# Top_module.net
KiCad netlist of a schematic drawn in EAGLE
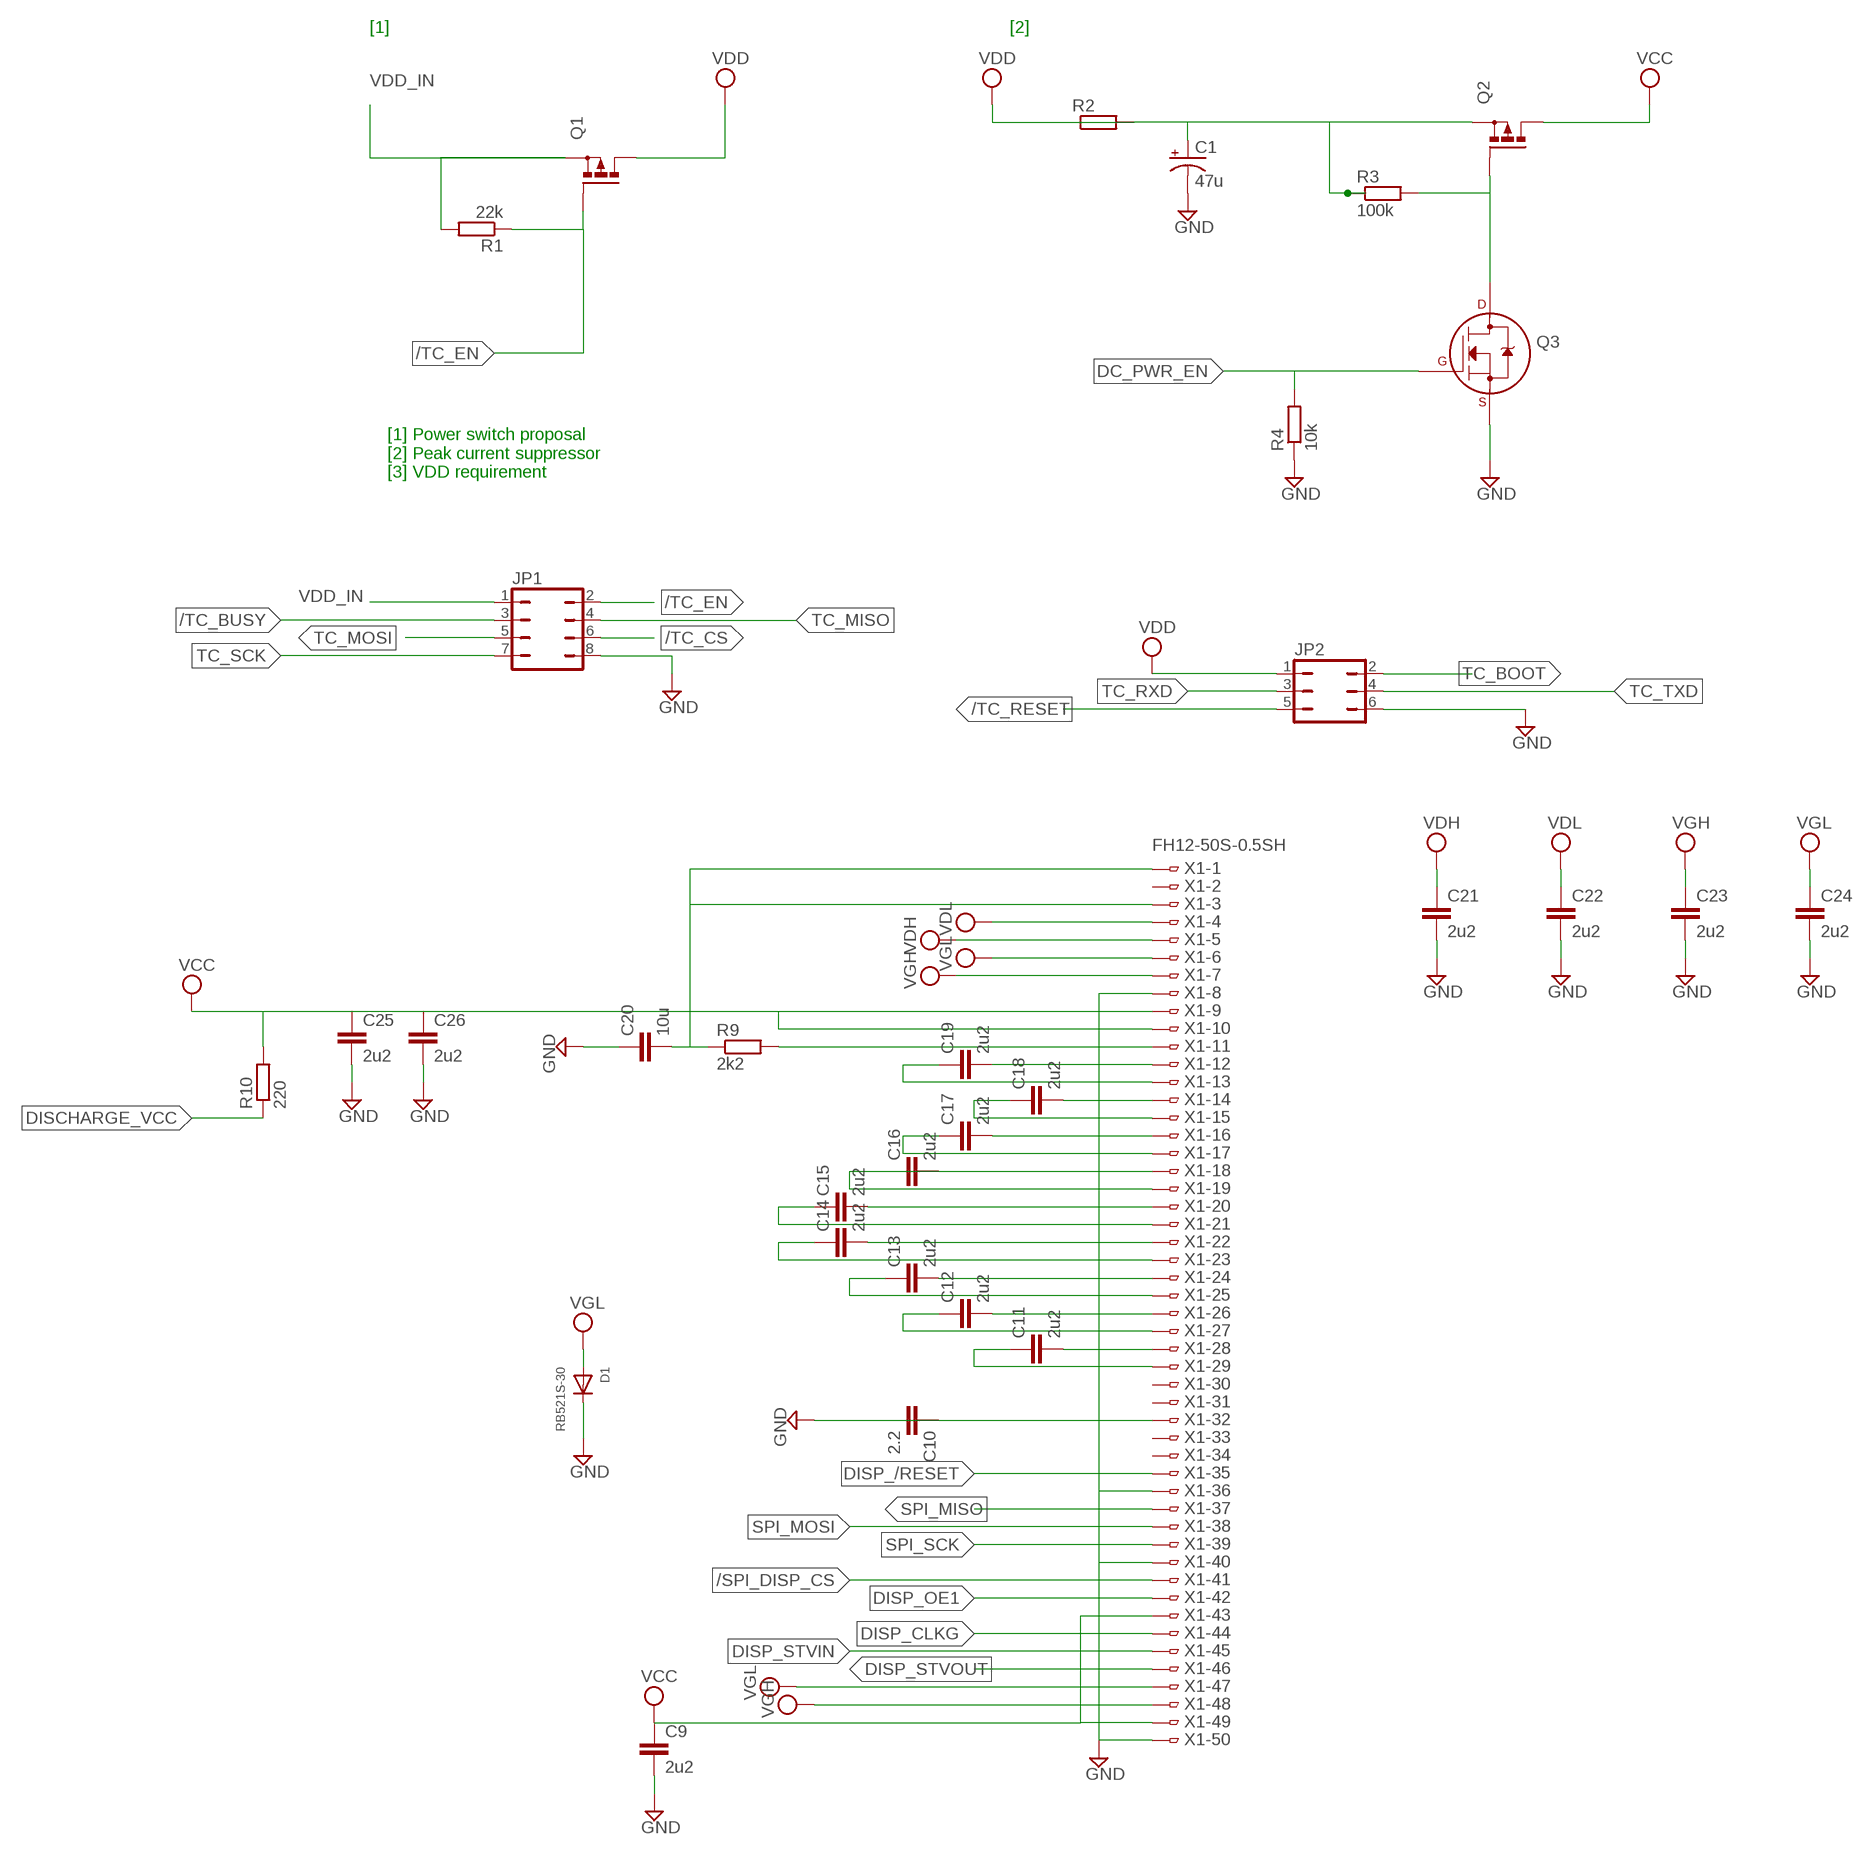
[diagram p0: schematic, sheet 1, part 1 of 2]
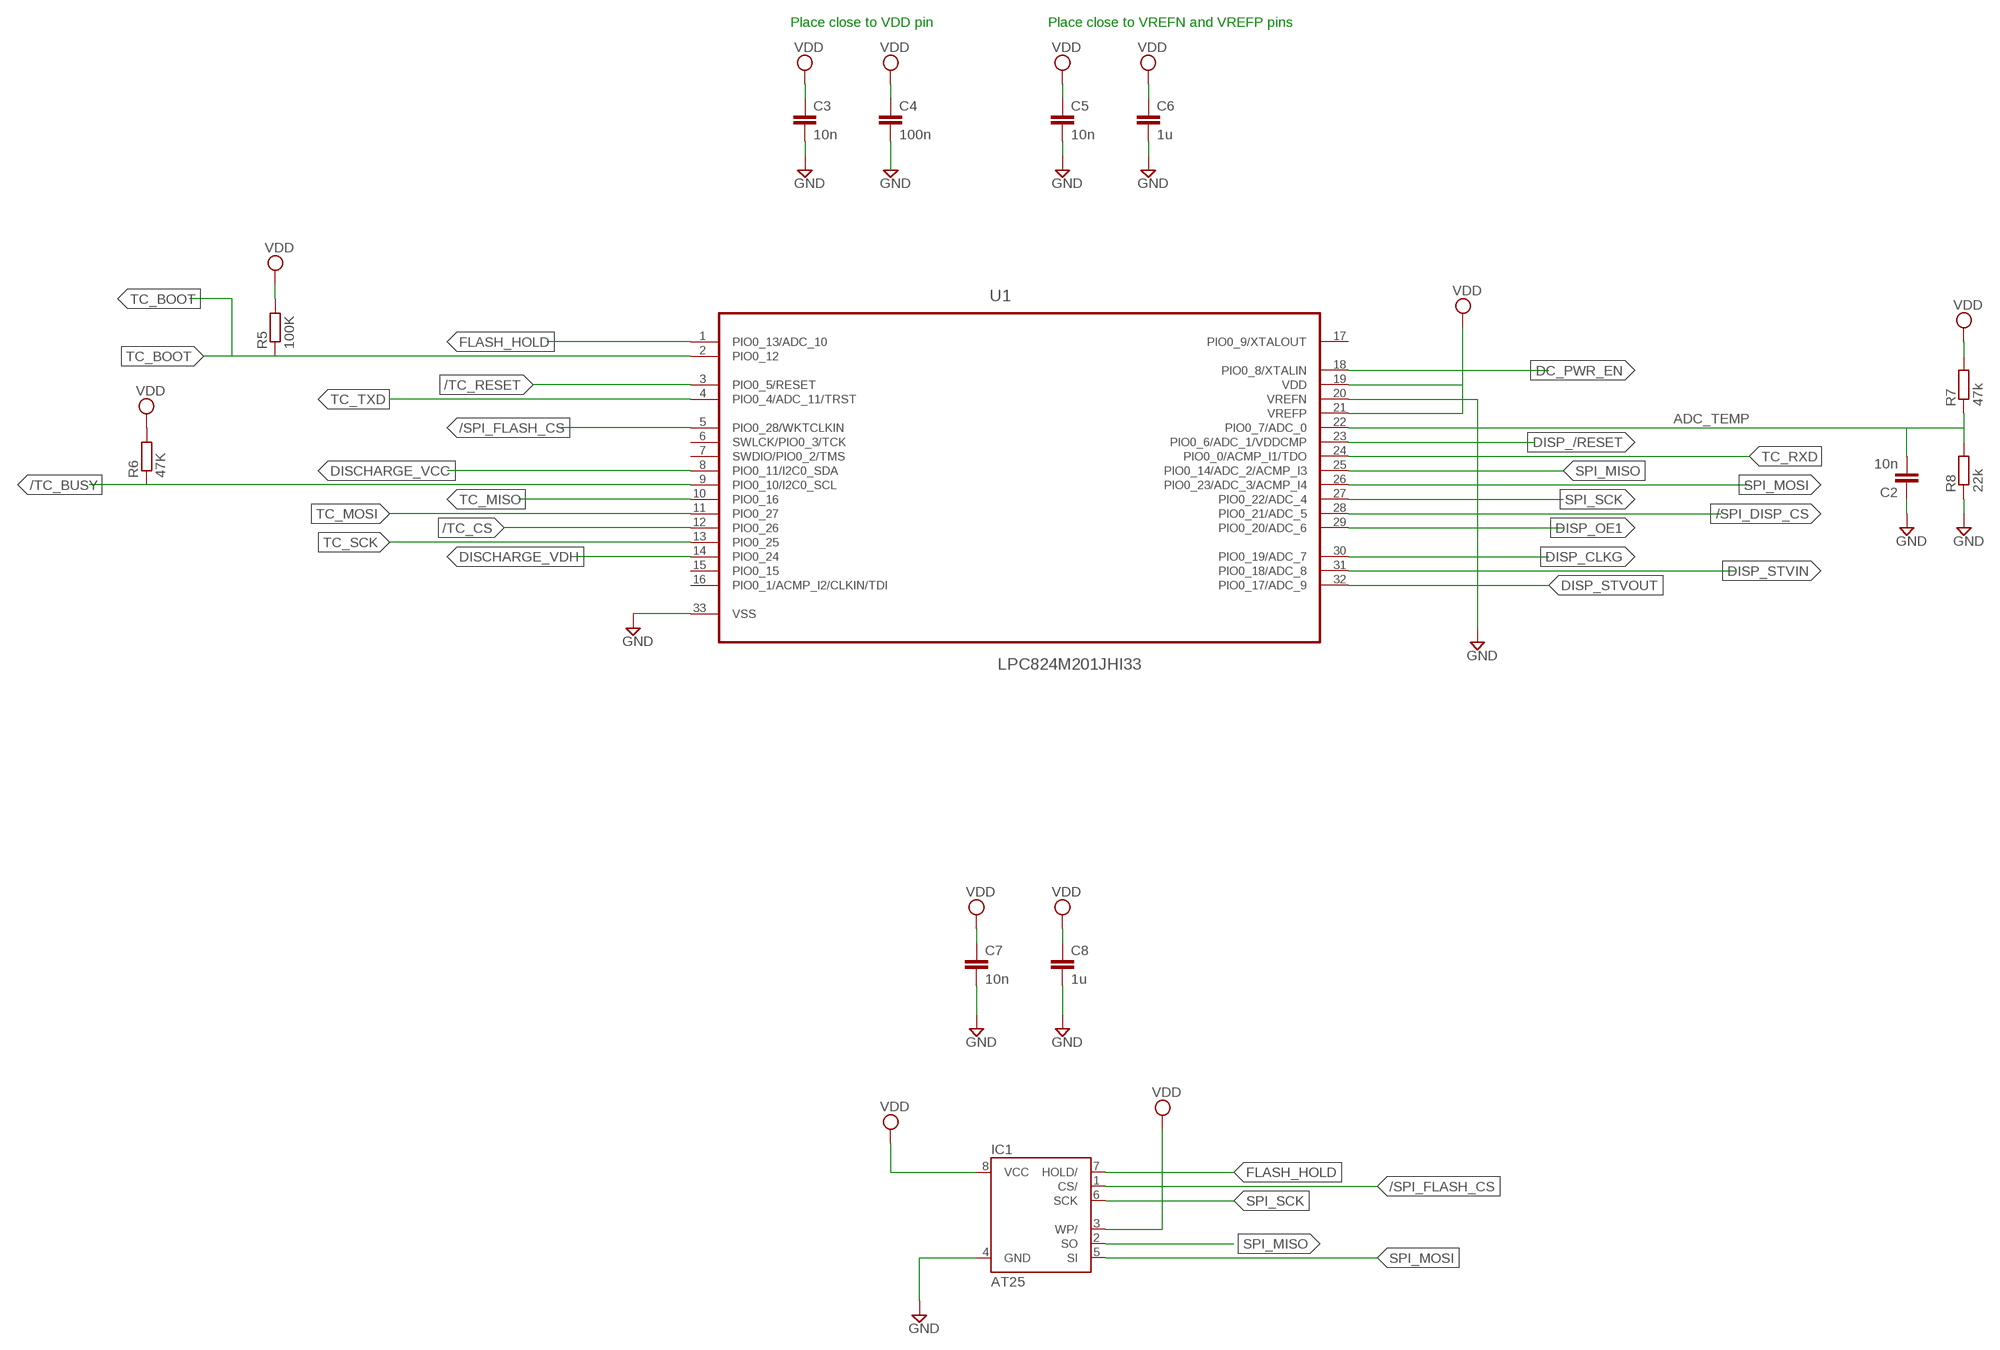
[diagram p1: schematic, sheet 1, part 2 of 2]

(export (version "E")
  (design (tool "Eeschema 10.0.6"))
  (components
    (comp (ref "C1")
      (value "47u")
      (footprint "eagle-import:B_3528-21R")
      (libsource (lib "eagle-import") (part "CPOL-USB/3528-21R"))
    )
    (comp (ref "C2")
      (value "10n")
      (footprint "eagle-import:C0603")
      (libsource (lib "eagle-import") (part "resistor_C-EUC0603"))
    )
    (comp (ref "C3")
      (value "10n")
      (footprint "eagle-import:C0603")
      (libsource (lib "eagle-import") (part "C-EUC0603"))
    )
    (comp (ref "C4")
      (value "100n")
      (footprint "eagle-import:C0603")
      (libsource (lib "eagle-import") (part "C-EUC0603"))
    )
    (comp (ref "C5")
      (value "10n")
      (footprint "eagle-import:C0603")
      (libsource (lib "eagle-import") (part "C-EUC0603"))
    )
    (comp (ref "C6")
      (value "1u")
      (footprint "eagle-import:C0603")
      (libsource (lib "eagle-import") (part "C-EUC0603"))
    )
    (comp (ref "C7")
      (value "10n")
      (footprint "eagle-import:C0603")
      (libsource (lib "eagle-import") (part "C-EUC0603"))
    )
    (comp (ref "C8")
      (value "1u")
      (footprint "eagle-import:C0603")
      (libsource (lib "eagle-import") (part "C-EUC0603"))
    )
    (comp (ref "C9")
      (value "2u2")
      (footprint "eagle-import:C0603")
      (libsource (lib "eagle-import") (part "C-EUC0603"))
    )
    (comp (ref "C10")
      (value "2.2")
      (footprint "eagle-import:C0603")
      (libsource (lib "eagle-import") (part "C-EUC0603"))
    )
    (comp (ref "C11")
      (value "2u2")
      (footprint "eagle-import:C1608")
      (libsource (lib "eagle-import") (part "C-EUC1608"))
    )
    (comp (ref "C12")
      (value "2u2")
      (footprint "eagle-import:C1608")
      (libsource (lib "eagle-import") (part "C-EUC1608"))
    )
    (comp (ref "C13")
      (value "2u2")
      (footprint "eagle-import:C1608")
      (libsource (lib "eagle-import") (part "C-EUC1608"))
    )
    (comp (ref "C14")
      (value "2u2")
      (footprint "eagle-import:C1608")
      (libsource (lib "eagle-import") (part "C-EUC1608"))
    )
    (comp (ref "C15")
      (value "2u2")
      (footprint "eagle-import:C1608")
      (libsource (lib "eagle-import") (part "C-EUC1608"))
    )
    (comp (ref "C16")
      (value "2u2")
      (footprint "eagle-import:C1608")
      (libsource (lib "eagle-import") (part "C-EUC1608"))
    )
    (comp (ref "C17")
      (value "2u2")
      (footprint "eagle-import:C1608")
      (libsource (lib "eagle-import") (part "C-EUC1608"))
    )
    (comp (ref "C18")
      (value "2u2")
      (footprint "eagle-import:C1608")
      (libsource (lib "eagle-import") (part "C-EUC1608"))
    )
    (comp (ref "C19")
      (value "2u2")
      (footprint "eagle-import:C1608")
      (libsource (lib "eagle-import") (part "C-EUC1608"))
    )
    (comp (ref "C20")
      (value "10u")
      (footprint "eagle-import:C1608")
      (libsource (lib "eagle-import") (part "C-EUC1608"))
    )
    (comp (ref "C21")
      (value "2u2")
      (footprint "eagle-import:C1608")
      (libsource (lib "eagle-import") (part "C-EUC1608"))
    )
    (comp (ref "C22")
      (value "2u2")
      (footprint "eagle-import:C1608")
      (libsource (lib "eagle-import") (part "C-EUC1608"))
    )
    (comp (ref "C23")
      (value "2u2")
      (footprint "eagle-import:C1608")
      (libsource (lib "eagle-import") (part "C-EUC1608"))
    )
    (comp (ref "C24")
      (value "2u2")
      (footprint "eagle-import:C1608")
      (libsource (lib "eagle-import") (part "C-EUC1608"))
    )
    (comp (ref "C25")
      (value "2u2")
      (footprint "eagle-import:C1608")
      (libsource (lib "eagle-import") (part "C-EUC1608"))
    )
    (comp (ref "C26")
      (value "2u2")
      (footprint "eagle-import:C1608")
      (libsource (lib "eagle-import") (part "C-EUC1608"))
    )
    (comp (ref "D1")
      (value "RB521S-30")
      (footprint "eagle-import:SOD-523")
      (libsource (lib "eagle-import") (part "DIODESOD-523"))
    )
    (comp (ref "IC1")
      (value "AT25")
      (footprint "eagle-import:SOIC8")
      (libsource (lib "eagle-import") (part "AT25"))
    )
    (comp (ref "JP1")
      (value "JP4Q")
      (footprint "eagle-import:JP4Q")
      (libsource (lib "eagle-import") (part "JP4Q"))
    )
    (comp (ref "JP2")
      (value "JP3Q")
      (footprint "eagle-import:JP3Q")
      (libsource (lib "eagle-import") (part "JP3Q"))
    )
    (comp (ref "Q1")
      (value "NTR4171PTG")
      (footprint "eagle-import:SOT23")
      (libsource (lib "eagle-import") (part "NTR4171PTG"))
    )
    (comp (ref "Q2")
      (value "NTR4171PTG")
      (footprint "eagle-import:SOT23")
      (libsource (lib "eagle-import") (part "NTR4171PTG"))
    )
    (comp (ref "Q3")
      (value "2N7002_SOT23")
      (footprint "eagle-import:SOT-23")
      (libsource (lib "eagle-import") (part "2N700_SOT232"))
    )
    (comp (ref "R1")
      (value "22k")
      (footprint "eagle-import:R0603")
      (libsource (lib "eagle-import") (part "resistor_R-EU_R0603"))
    )
    (comp (ref "R2")
      (value "R-EU_R0603")
      (footprint "eagle-import:R0603")
      (libsource (lib "eagle-import") (part "R-EU_R0603"))
    )
    (comp (ref "R3")
      (value "100k")
      (footprint "eagle-import:R0603")
      (libsource (lib "eagle-import") (part "R-EU_R0603"))
    )
    (comp (ref "R4")
      (value "10k")
      (footprint "eagle-import:R0603")
      (libsource (lib "eagle-import") (part "R-EU_R0603"))
    )
    (comp (ref "R5")
      (value "100K")
      (footprint "eagle-import:R0603")
      (libsource (lib "eagle-import") (part "resistor_R-EU_R0603"))
    )
    (comp (ref "R6")
      (value "47K")
      (footprint "eagle-import:R0603")
      (libsource (lib "eagle-import") (part "R-EU_R0603"))
    )
    (comp (ref "R7")
      (value "47k")
      (footprint "eagle-import:R0603")
      (libsource (lib "eagle-import") (part "resistor_R-EU_R0603"))
    )
    (comp (ref "R8")
      (value "22k")
      (footprint "eagle-import:R0603")
      (libsource (lib "eagle-import") (part "resistor_R-EU_R0603"))
    )
    (comp (ref "R9")
      (value "2k2")
      (footprint "eagle-import:R0603")
      (libsource (lib "eagle-import") (part "R-EU_R0603"))
    )
    (comp (ref "R10")
      (value "220")
      (footprint "eagle-import:R0603")
      (libsource (lib "eagle-import") (part "resistor_R-EU_R0603"))
    )
    (comp (ref "U1")
      (value "LPC824M201JHI33")
      (footprint "eagle-import:QFN65P700X700X100-33N")
      (fields (field (name "MPN") "LPC1114FHN33/201,5"))
      (libsource (lib "eagle-import") (part "LPC824M201JHI33"))
    )
    (comp (ref "X1")
      (value "FH12-50S-0.5SH")
      (footprint "eagle-import:FH12-50S-0.5SH")
      (fields (field (name "MPN") "FH12-50S-0.5SH(55)"))
      (libsource (lib "eagle-import") (part "FH12-50S-0.5SH"))
    )
  )
  (nets
    (net (code "1") (name "/ADC_TEMP") (class "Default")
      (node (ref "C2") (pin "2") (pinfunction "2_2") (pintype "passive"))
      (node (ref "R7") (pin "1") (pinfunction "1_1") (pintype "passive"))
      (node (ref "R8") (pin "2") (pinfunction "2_2") (pintype "passive"))
      (node (ref "U1") (pin "22") (pinfunction "PIO0_7/ADC_0_22") (pintype "bidirectional"))
    )
    (net (code "2") (name "/VDD_IN") (class "Default")
      (node (ref "JP1") (pin "1") (pinfunction "1_1") (pintype "passive"))
      (node (ref "Q1") (pin "S") (pinfunction "S_S") (pintype "passive"))
      (node (ref "R1") (pin "2") (pinfunction "2_2") (pintype "passive"))
    )
    (net (code "3") (name "DC_PWR_EN") (class "Default")
      (node (ref "Q3") (pin "1") (pinfunction "G_1") (pintype "tri_state"))
      (node (ref "R4") (pin "2") (pinfunction "2_2") (pintype "passive"))
      (node (ref "U1") (pin "18") (pinfunction "PIO0_8/XTALIN_18") (pintype "bidirectional"))
    )
    (net (code "4") (name "DISCHARGE_VCC") (class "Default")
      (node (ref "R10") (pin "1") (pinfunction "1_1") (pintype "passive"))
      (node (ref "U1") (pin "8") (pinfunction "PIO0_11/I2C0_SDA_8") (pintype "bidirectional"))
    )
    (net (code "5") (name "DISCHARGE_VDH") (class "Default")
      (node (ref "U1") (pin "14") (pinfunction "PIO0_24_14") (pintype "bidirectional"))
    )
    (net (code "6") (name "DISP_CLKG") (class "Default")
      (node (ref "U1") (pin "30") (pinfunction "PIO0_19/ADC_7_30") (pintype "bidirectional"))
      (node (ref "X1") (pin "44") (pinfunction "1_44") (pintype "passive"))
    )
    (net (code "7") (name "DISP_OE1") (class "Default")
      (node (ref "U1") (pin "29") (pinfunction "PIO0_20/ADC_6_29") (pintype "bidirectional"))
      (node (ref "X1") (pin "42") (pinfunction "1_42") (pintype "passive"))
    )
    (net (code "8") (name "DISP_STVIN") (class "Default")
      (node (ref "U1") (pin "31") (pinfunction "PIO0_18/ADC_8_31") (pintype "bidirectional"))
      (node (ref "X1") (pin "45") (pinfunction "1_45") (pintype "passive"))
    )
    (net (code "9") (name "DISP_STVOUT") (class "Default")
      (node (ref "U1") (pin "32") (pinfunction "PIO0_17/ADC_9_32") (pintype "bidirectional"))
      (node (ref "X1") (pin "46") (pinfunction "1_46") (pintype "passive"))
    )
    (net (code "10") (name "DISP_{slash}RESET") (class "Default")
      (node (ref "U1") (pin "23") (pinfunction "PIO0_6/ADC_1/VDDCMP_23") (pintype "bidirectional"))
      (node (ref "X1") (pin "35") (pinfunction "1_35") (pintype "passive"))
    )
    (net (code "11") (name "FLASH_HOLD") (class "Default")
      (node (ref "IC1") (pin "7") (pinfunction "HOLD/_7") (pintype "input"))
      (node (ref "U1") (pin "1") (pinfunction "PIO0_13/ADC_10_1") (pintype "bidirectional"))
    )
    (net (code "12") (name "GND") (class "Default")
      (node (ref "C1") (pin "-") (pinfunction "-_-") (pintype "passive"))
      (node (ref "C10") (pin "1") (pinfunction "1_1") (pintype "passive"))
      (node (ref "C10") (pin "2") (pinfunction "2_2") (pintype "passive"))
      (node (ref "C2") (pin "1") (pinfunction "1_1") (pintype "passive"))
      (node (ref "C20") (pin "1") (pinfunction "1_1") (pintype "passive"))
      (node (ref "C21") (pin "2") (pinfunction "2_2") (pintype "passive"))
      (node (ref "C22") (pin "2") (pinfunction "2_2") (pintype "passive"))
      (node (ref "C23") (pin "2") (pinfunction "2_2") (pintype "passive"))
      (node (ref "C24") (pin "2") (pinfunction "2_2") (pintype "passive"))
      (node (ref "C25") (pin "2") (pinfunction "2_2") (pintype "passive"))
      (node (ref "C26") (pin "2") (pinfunction "2_2") (pintype "passive"))
      (node (ref "C3") (pin "2") (pinfunction "2_2") (pintype "passive"))
      (node (ref "C5") (pin "2") (pinfunction "2_2") (pintype "passive"))
      (node (ref "C6") (pin "2") (pinfunction "2_2") (pintype "passive"))
      (node (ref "C7") (pin "2") (pinfunction "2_2") (pintype "passive"))
      (node (ref "C8") (pin "2") (pinfunction "2_2") (pintype "passive"))
      (node (ref "C9") (pin "2") (pinfunction "2_2") (pintype "passive"))
      (node (ref "D1") (pin "K") (pinfunction "C_K") (pintype "passive"))
      (node (ref "IC1") (pin "4") (pinfunction "GND_4") (pintype "power_in"))
      (node (ref "JP1") (pin "8") (pinfunction "8_8") (pintype "passive"))
      (node (ref "JP2") (pin "6") (pinfunction "6_6") (pintype "passive"))
      (node (ref "Q3") (pin "2") (pinfunction "S_2") (pintype "bidirectional"))
      (node (ref "R4") (pin "1") (pinfunction "1_1") (pintype "passive"))
      (node (ref "R8") (pin "1") (pinfunction "1_1") (pintype "passive"))
      (node (ref "U1") (pin "20") (pinfunction "VREFN_20") (pintype "power_in"))
      (node (ref "U1") (pin "33") (pinfunction "VSS_33") (pintype "passive"))
      (node (ref "X1") (pin "32") (pinfunction "1_32") (pintype "passive"))
      (node (ref "X1") (pin "36") (pinfunction "1_36") (pintype "passive"))
      (node (ref "X1") (pin "40") (pinfunction "1_40") (pintype "passive"))
      (node (ref "X1") (pin "50") (pinfunction "1_50") (pintype "passive"))
      (node (ref "X1") (pin "8") (pinfunction "1_8") (pintype "passive"))
    )
    (net (code "13") (name "Net-(Q3-D)") (class "Default")
      (node (ref "Q2") (pin "G") (pinfunction "G_G") (pintype "passive"))
      (node (ref "Q3") (pin "3") (pinfunction "D_3") (pintype "bidirectional"))
      (node (ref "R3") (pin "2") (pinfunction "2_2") (pintype "passive"))
    )
    (net (code "14") (name "Net-(X1C-1)") (class "Default")
      (node (ref "R9") (pin "2") (pinfunction "2_2") (pintype "passive"))
      (node (ref "X1") (pin "11") (pinfunction "1_11") (pintype "passive"))
    )
    (net (code "15") (name "Net-(X1D-1)") (class "Default")
      (node (ref "C19") (pin "2") (pinfunction "2_2") (pintype "passive"))
      (node (ref "X1") (pin "12") (pinfunction "1_12") (pintype "passive"))
    )
    (net (code "16") (name "Net-(X1E-1)") (class "Default")
      (node (ref "C19") (pin "1") (pinfunction "1_1") (pintype "passive"))
      (node (ref "X1") (pin "13") (pinfunction "1_13") (pintype "passive"))
    )
    (net (code "17") (name "Net-(X1F-1)") (class "Default")
      (node (ref "C18") (pin "2") (pinfunction "2_2") (pintype "passive"))
      (node (ref "X1") (pin "14") (pinfunction "1_14") (pintype "passive"))
    )
    (net (code "18") (name "Net-(X1G-1)") (class "Default")
      (node (ref "C18") (pin "1") (pinfunction "1_1") (pintype "passive"))
      (node (ref "X1") (pin "15") (pinfunction "1_15") (pintype "passive"))
    )
    (net (code "19") (name "Net-(X1H-1)") (class "Default")
      (node (ref "C17") (pin "2") (pinfunction "2_2") (pintype "passive"))
      (node (ref "X1") (pin "16") (pinfunction "1_16") (pintype "passive"))
    )
    (net (code "20") (name "Net-(X1I-1)") (class "Default")
      (node (ref "C17") (pin "1") (pinfunction "1_1") (pintype "passive"))
      (node (ref "X1") (pin "17") (pinfunction "1_17") (pintype "passive"))
    )
    (net (code "21") (name "Net-(X1J-1)") (class "Default")
      (node (ref "C16") (pin "1") (pinfunction "1_1") (pintype "passive"))
      (node (ref "C16") (pin "2") (pinfunction "2_2") (pintype "passive"))
      (node (ref "X1") (pin "18") (pinfunction "1_18") (pintype "passive"))
      (node (ref "X1") (pin "19") (pinfunction "1_19") (pintype "passive"))
    )
    (net (code "22") (name "Net-(X1M-1)") (class "Default")
      (node (ref "C15") (pin "2") (pinfunction "2_2") (pintype "passive"))
      (node (ref "X1") (pin "20") (pinfunction "1_20") (pintype "passive"))
    )
    (net (code "23") (name "Net-(X1N-1)") (class "Default")
      (node (ref "C15") (pin "1") (pinfunction "1_1") (pintype "passive"))
      (node (ref "X1") (pin "21") (pinfunction "1_21") (pintype "passive"))
    )
    (net (code "24") (name "Net-(X1O-1)") (class "Default")
      (node (ref "C14") (pin "2") (pinfunction "2_2") (pintype "passive"))
      (node (ref "X1") (pin "22") (pinfunction "1_22") (pintype "passive"))
    )
    (net (code "25") (name "Net-(X1P-1)") (class "Default")
      (node (ref "C14") (pin "1") (pinfunction "1_1") (pintype "passive"))
      (node (ref "X1") (pin "23") (pinfunction "1_23") (pintype "passive"))
    )
    (net (code "26") (name "Net-(X1Q-1)") (class "Default")
      (node (ref "C13") (pin "2") (pinfunction "2_2") (pintype "passive"))
      (node (ref "X1") (pin "24") (pinfunction "1_24") (pintype "passive"))
    )
    (net (code "27") (name "Net-(X1R-1)") (class "Default")
      (node (ref "C13") (pin "1") (pinfunction "1_1") (pintype "passive"))
      (node (ref "X1") (pin "25") (pinfunction "1_25") (pintype "passive"))
    )
    (net (code "28") (name "Net-(X1S-1)") (class "Default")
      (node (ref "C12") (pin "2") (pinfunction "2_2") (pintype "passive"))
      (node (ref "X1") (pin "26") (pinfunction "1_26") (pintype "passive"))
    )
    (net (code "29") (name "Net-(X1T-1)") (class "Default")
      (node (ref "C12") (pin "1") (pinfunction "1_1") (pintype "passive"))
      (node (ref "X1") (pin "27") (pinfunction "1_27") (pintype "passive"))
    )
    (net (code "30") (name "Net-(X1U-1)") (class "Default")
      (node (ref "C11") (pin "2") (pinfunction "2_2") (pintype "passive"))
      (node (ref "X1") (pin "28") (pinfunction "1_28") (pintype "passive"))
    )
    (net (code "31") (name "Net-(X1V-1)") (class "Default")
      (node (ref "C11") (pin "1") (pinfunction "1_1") (pintype "passive"))
      (node (ref "X1") (pin "29") (pinfunction "1_29") (pintype "passive"))
    )
    (net (code "32") (name "Net-(X1W-1)") (class "Default")
      (node (ref "C20") (pin "2") (pinfunction "2_2") (pintype "passive"))
      (node (ref "R9") (pin "1") (pinfunction "1_1") (pintype "passive"))
      (node (ref "X1") (pin "1") (pinfunction "1_1") (pintype "passive"))
      (node (ref "X1") (pin "3") (pinfunction "1_3") (pintype "passive"))
    )
    (net (code "33") (name "SPI_MISO") (class "Default")
      (node (ref "IC1") (pin "2") (pinfunction "SO_2") (pintype "input"))
      (node (ref "U1") (pin "25") (pinfunction "PIO0_14/ADC_2/ACMP_I3_25") (pintype "bidirectional"))
      (node (ref "X1") (pin "37") (pinfunction "1_37") (pintype "passive"))
    )
    (net (code "34") (name "SPI_MOSI") (class "Default")
      (node (ref "IC1") (pin "5") (pinfunction "SI_5") (pintype "bidirectional"))
      (node (ref "U1") (pin "26") (pinfunction "PIO0_23/ADC_3/ACMP_I4_26") (pintype "bidirectional"))
      (node (ref "X1") (pin "38") (pinfunction "1_38") (pintype "passive"))
    )
    (net (code "35") (name "SPI_SCK") (class "Default")
      (node (ref "IC1") (pin "6") (pinfunction "SCK_6") (pintype "bidirectional"))
      (node (ref "U1") (pin "27") (pinfunction "PIO0_22/ADC_4_27") (pintype "bidirectional"))
      (node (ref "X1") (pin "39") (pinfunction "1_39") (pintype "passive"))
    )
    (net (code "36") (name "TC_BOOT") (class "Default")
      (node (ref "JP2") (pin "2") (pinfunction "2_2") (pintype "passive"))
      (node (ref "R5") (pin "1") (pinfunction "1_1") (pintype "passive"))
      (node (ref "U1") (pin "2") (pinfunction "PIO0_12_2") (pintype "bidirectional"))
    )
    (net (code "37") (name "TC_MISO") (class "Default")
      (node (ref "JP1") (pin "4") (pinfunction "4_4") (pintype "passive"))
      (node (ref "U1") (pin "10") (pinfunction "PIO0_16_10") (pintype "bidirectional"))
    )
    (net (code "38") (name "TC_MOSI") (class "Default")
      (node (ref "JP1") (pin "5") (pinfunction "5_5") (pintype "passive"))
      (node (ref "U1") (pin "11") (pinfunction "PIO0_27_11") (pintype "bidirectional"))
    )
    (net (code "39") (name "TC_RXD") (class "Default")
      (node (ref "JP2") (pin "3") (pinfunction "3_3") (pintype "passive"))
      (node (ref "U1") (pin "24") (pinfunction "PIO0_0/ACMP_I1/TDO_24") (pintype "bidirectional"))
    )
    (net (code "40") (name "TC_SCK") (class "Default")
      (node (ref "JP1") (pin "7") (pinfunction "7_7") (pintype "passive"))
      (node (ref "U1") (pin "13") (pinfunction "PIO0_25_13") (pintype "bidirectional"))
    )
    (net (code "41") (name "TC_TXD") (class "Default")
      (node (ref "JP2") (pin "4") (pinfunction "4_4") (pintype "passive"))
      (node (ref "U1") (pin "4") (pinfunction "PIO0_4/ADC_11/TRST_4") (pintype "bidirectional"))
    )
    (net (code "42") (name "VCC") (class "Default")
      (node (ref "C25") (pin "1") (pinfunction "1_1") (pintype "passive"))
      (node (ref "C26") (pin "1") (pinfunction "1_1") (pintype "passive"))
      (node (ref "C9") (pin "1") (pinfunction "1_1") (pintype "passive"))
      (node (ref "Q2") (pin "D") (pinfunction "D_D") (pintype "passive"))
      (node (ref "R10") (pin "2") (pinfunction "2_2") (pintype "passive"))
      (node (ref "X1") (pin "10") (pinfunction "1_10") (pintype "passive"))
      (node (ref "X1") (pin "43") (pinfunction "1_43") (pintype "passive"))
      (node (ref "X1") (pin "49") (pinfunction "1_49") (pintype "passive"))
      (node (ref "X1") (pin "9") (pinfunction "1_9") (pintype "passive"))
    )
    (net (code "43") (name "VDD") (class "Default")
      (node (ref "C1") (pin "+") (pinfunction "+_+") (pintype "passive"))
      (node (ref "C3") (pin "1") (pinfunction "1_1") (pintype "passive"))
      (node (ref "C4") (pin "1") (pinfunction "1_1") (pintype "passive"))
      (node (ref "C5") (pin "1") (pinfunction "1_1") (pintype "passive"))
      (node (ref "C6") (pin "1") (pinfunction "1_1") (pintype "passive"))
      (node (ref "C7") (pin "1") (pinfunction "1_1") (pintype "passive"))
      (node (ref "C8") (pin "1") (pinfunction "1_1") (pintype "passive"))
      (node (ref "IC1") (pin "3") (pinfunction "WP/_3") (pintype "input"))
      (node (ref "IC1") (pin "8") (pinfunction "VCC_8") (pintype "power_in"))
      (node (ref "JP2") (pin "1") (pinfunction "1_1") (pintype "passive"))
      (node (ref "Q1") (pin "D") (pinfunction "D_D") (pintype "passive"))
      (node (ref "Q2") (pin "S") (pinfunction "S_S") (pintype "passive"))
      (node (ref "R2") (pin "1") (pinfunction "1_1") (pintype "passive"))
      (node (ref "R2") (pin "2") (pinfunction "2_2") (pintype "passive"))
      (node (ref "R3") (pin "1") (pinfunction "1_1") (pintype "passive"))
      (node (ref "R5") (pin "2") (pinfunction "2_2") (pintype "passive"))
      (node (ref "R6") (pin "2") (pinfunction "2_2") (pintype "passive"))
      (node (ref "R7") (pin "2") (pinfunction "2_2") (pintype "passive"))
      (node (ref "U1") (pin "19") (pinfunction "VDD_19") (pintype "power_in"))
      (node (ref "U1") (pin "21") (pinfunction "VREFP_21") (pintype "power_in"))
    )
    (net (code "44") (name "VDH") (class "Default")
      (node (ref "C21") (pin "1") (pinfunction "1_1") (pintype "passive"))
      (node (ref "X1") (pin "5") (pinfunction "1_5") (pintype "passive"))
    )
    (net (code "45") (name "VDL") (class "Default")
      (node (ref "C22") (pin "1") (pinfunction "1_1") (pintype "passive"))
      (node (ref "X1") (pin "4") (pinfunction "1_4") (pintype "passive"))
    )
    (net (code "46") (name "VGH") (class "Default")
      (node (ref "C23") (pin "1") (pinfunction "1_1") (pintype "passive"))
      (node (ref "X1") (pin "48") (pinfunction "1_48") (pintype "passive"))
      (node (ref "X1") (pin "7") (pinfunction "1_7") (pintype "passive"))
    )
    (net (code "47") (name "VGL") (class "Default")
      (node (ref "C24") (pin "1") (pinfunction "1_1") (pintype "passive"))
      (node (ref "D1") (pin "A") (pinfunction "A_A") (pintype "passive"))
      (node (ref "X1") (pin "47") (pinfunction "1_47") (pintype "passive"))
      (node (ref "X1") (pin "6") (pinfunction "1_6") (pintype "passive"))
    )
    (net (code "48") (name "unconnected-(C4-Pad2)") (class "Default")
      (node (ref "C4") (pin "2") (pinfunction "2_2") (pintype "passive"))
    )
    (net (code "49") (name "unconnected-(U1-PIO0_1{slash}ACMP_I2{slash}CLKIN{slash}TDI-Pad16)") (class "Default")
      (node (ref "U1") (pin "16") (pinfunction "PIO0_1/ACMP_I2/CLKIN/TDI_16") (pintype "no_connect"))
    )
    (net (code "50") (name "unconnected-(U1-PIO0_9{slash}XTALOUT-Pad17)") (class "Default")
      (node (ref "U1") (pin "17") (pinfunction "PIO0_9/XTALOUT_17") (pintype "no_connect"))
    )
    (net (code "51") (name "unconnected-(U1-PIO0_15-Pad15)") (class "Default")
      (node (ref "U1") (pin "15") (pinfunction "PIO0_15_15") (pintype "no_connect"))
    )
    (net (code "52") (name "unconnected-(U1-SWDIO{slash}PIO0_2{slash}TMS-Pad7)") (class "Default")
      (node (ref "U1") (pin "7") (pinfunction "SWDIO/PIO0_2/TMS_7") (pintype "no_connect"))
    )
    (net (code "53") (name "unconnected-(U1-SWLCK{slash}PIO0_3{slash}TCK-Pad6)") (class "Default")
      (node (ref "U1") (pin "6") (pinfunction "SWLCK/PIO0_3/TCK_6") (pintype "no_connect"))
    )
    (net (code "54") (name "unconnected-(X1AA-1-Pad33)") (class "Default")
      (node (ref "X1") (pin "33") (pinfunction "1_33") (pintype "passive"))
    )
    (net (code "55") (name "unconnected-(X1AB-1-Pad34)") (class "Default")
      (node (ref "X1") (pin "34") (pinfunction "1_34") (pintype "passive"))
    )
    (net (code "56") (name "unconnected-(X1L-1-Pad2)") (class "Default")
      (node (ref "X1") (pin "2") (pinfunction "1_2") (pintype "passive"))
    )
    (net (code "57") (name "unconnected-(X1X-1-Pad30)") (class "Default")
      (node (ref "X1") (pin "30") (pinfunction "1_30") (pintype "passive"))
    )
    (net (code "58") (name "unconnected-(X1Y-1-Pad31)") (class "Default")
      (node (ref "X1") (pin "31") (pinfunction "1_31") (pintype "passive"))
    )
    (net (code "59") (name "{slash}SPI_DISP_CS") (class "Default")
      (node (ref "U1") (pin "28") (pinfunction "PIO0_21/ADC_5_28") (pintype "bidirectional"))
      (node (ref "X1") (pin "41") (pinfunction "1_41") (pintype "passive"))
    )
    (net (code "60") (name "{slash}SPI_FLASH_CS") (class "Default")
      (node (ref "IC1") (pin "1") (pinfunction "CS/_1") (pintype "input"))
      (node (ref "U1") (pin "5") (pinfunction "PIO0_28/WKTCLKIN_5") (pintype "bidirectional"))
    )
    (net (code "61") (name "{slash}TC_BUSY") (class "Default")
      (node (ref "JP1") (pin "3") (pinfunction "3_3") (pintype "passive"))
      (node (ref "R6") (pin "1") (pinfunction "1_1") (pintype "passive"))
      (node (ref "U1") (pin "9") (pinfunction "PIO0_10/I2C0_SCL_9") (pintype "bidirectional"))
    )
    (net (code "62") (name "{slash}TC_CS") (class "Default")
      (node (ref "JP1") (pin "6") (pinfunction "6_6") (pintype "passive"))
      (node (ref "U1") (pin "12") (pinfunction "PIO0_26_12") (pintype "bidirectional"))
    )
    (net (code "63") (name "{slash}TC_EN") (class "Default")
      (node (ref "JP1") (pin "2") (pinfunction "2_2") (pintype "passive"))
      (node (ref "Q1") (pin "G") (pinfunction "G_G") (pintype "passive"))
      (node (ref "R1") (pin "1") (pinfunction "1_1") (pintype "passive"))
    )
    (net (code "64") (name "{slash}TC_RESET") (class "Default")
      (node (ref "JP2") (pin "5") (pinfunction "5_5") (pintype "passive"))
      (node (ref "U1") (pin "3") (pinfunction "PIO0_5/RESET_3") (pintype "bidirectional"))
    )
  )
)
